# cubex_radio.net
KiCad netlist of a schematic drawn in EAGLE
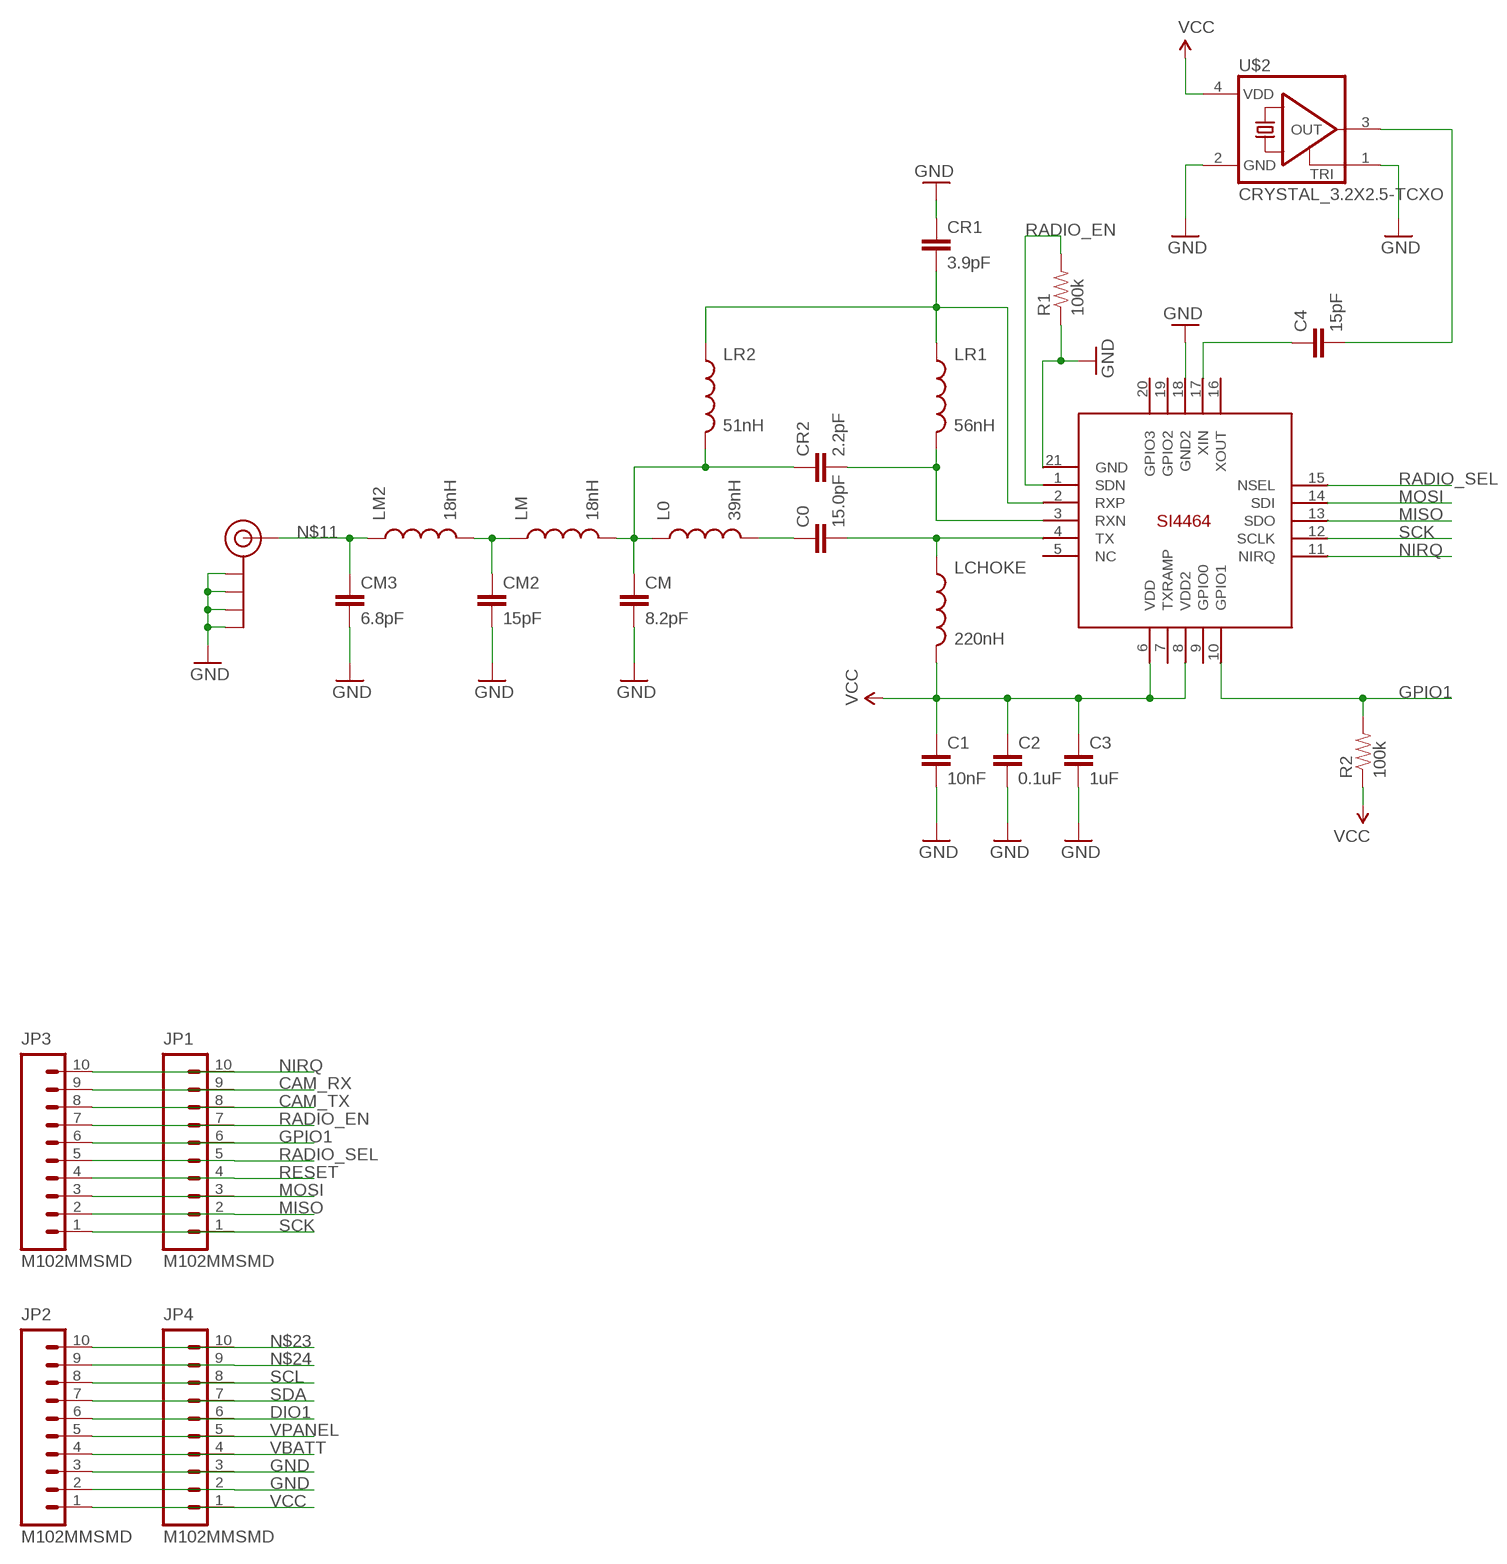
[diagram p0: schematic, sheet 1]

(export (version "E")
  (design (tool "Eeschema 10.0.6"))
  (components
    (comp (ref "C0")
      (value "15.0pF")
      (footprint "eagle-import:0805")
      (libsource (lib "eagle-import") (part "CAP0805"))
    )
    (comp (ref "C1")
      (value "10nF")
      (footprint "eagle-import:0805")
      (libsource (lib "eagle-import") (part "CAP0805"))
    )
    (comp (ref "C2")
      (value "0.1uF")
      (footprint "eagle-import:0805")
      (libsource (lib "eagle-import") (part "CAP0805"))
    )
    (comp (ref "C3")
      (value "1uF")
      (footprint "eagle-import:0805")
      (libsource (lib "eagle-import") (part "CAP0805"))
    )
    (comp (ref "C4")
      (value "15pF")
      (footprint "eagle-import:0805")
      (libsource (lib "eagle-import") (part "CAP0805"))
    )
    (comp (ref "CM")
      (value "8.2pF")
      (footprint "eagle-import:0805")
      (libsource (lib "eagle-import") (part "CAP0805"))
    )
    (comp (ref "CM2")
      (value "15pF")
      (footprint "eagle-import:0805")
      (libsource (lib "eagle-import") (part "CAP0805"))
    )
    (comp (ref "CM3")
      (value "6.8pF")
      (footprint "eagle-import:0805")
      (libsource (lib "eagle-import") (part "CAP0805"))
    )
    (comp (ref "CR1")
      (value "3.9pF")
      (footprint "eagle-import:0805")
      (libsource (lib "eagle-import") (part "CAP0805"))
    )
    (comp (ref "CR2")
      (value "2.2pF")
      (footprint "eagle-import:0805")
      (libsource (lib "eagle-import") (part "CAP0805"))
    )
    (comp (ref "J$1")
      (value "SMA_EDGE")
      (footprint "eagle-import:SMA-EDGE")
      (libsource (lib "eagle-import") (part "SMA_EDGE"))
    )
    (comp (ref "JP1")
      (value "M102MMSMD")
      (footprint "eagle-import:1X10-2MM-SMD")
      (libsource (lib "eagle-import") (part "M102MMSMD"))
    )
    (comp (ref "JP2")
      (value "M102MMSMD")
      (footprint "eagle-import:1X10-2MM-SMD")
      (libsource (lib "eagle-import") (part "M102MMSMD"))
    )
    (comp (ref "JP3")
      (value "M102MMSMD")
      (footprint "eagle-import:1X10-2MM-SMD")
      (libsource (lib "eagle-import") (part "M102MMSMD"))
    )
    (comp (ref "JP4")
      (value "M102MMSMD")
      (footprint "eagle-import:1X10-2MM-SMD")
      (libsource (lib "eagle-import") (part "M102MMSMD"))
    )
    (comp (ref "L0")
      (value "39nH")
      (footprint "eagle-import:0805")
      (libsource (lib "eagle-import") (part "INDUCTOR0805"))
    )
    (comp (ref "LCHOKE")
      (value "220nH")
      (footprint "eagle-import:0805")
      (libsource (lib "eagle-import") (part "INDUCTOR0805"))
    )
    (comp (ref "LM")
      (value "18nH")
      (footprint "eagle-import:0805")
      (libsource (lib "eagle-import") (part "INDUCTOR0805"))
    )
    (comp (ref "LM2")
      (value "18nH")
      (footprint "eagle-import:0805")
      (libsource (lib "eagle-import") (part "INDUCTOR0805"))
    )
    (comp (ref "LR1")
      (value "56nH")
      (footprint "eagle-import:0805")
      (libsource (lib "eagle-import") (part "INDUCTOR0805"))
    )
    (comp (ref "LR2")
      (value "51nH")
      (footprint "eagle-import:0805")
      (libsource (lib "eagle-import") (part "INDUCTOR0805"))
    )
    (comp (ref "R1")
      (value "100k")
      (footprint "eagle-import:0805")
      (libsource (lib "eagle-import") (part "RESISTOR0805-RES"))
    )
    (comp (ref "R2")
      (value "100k")
      (footprint "eagle-import:0805")
      (libsource (lib "eagle-import") (part "RESISTOR0805-RES"))
    )
    (comp (ref "U$1")
      (value "SI4464")
      (footprint "eagle-import:QFN20+GNDPAD")
      (libsource (lib "eagle-import") (part "SI4464"))
    )
    (comp (ref "U$2")
      (value "CRYSTAL_3.2X2.5-TCXO")
      (footprint "eagle-import:CRYSTAL_3.2X2.5-TCXO")
      (libsource (lib "eagle-import") (part "CRYSTAL_3.2X2.5-TCXO"))
    )
  )
  (nets
    (net (code "1") (name "/CAM_RX") (class "Default")
      (node (ref "JP1") (pin "9") (pinfunction "9_9") (pintype "passive"))
      (node (ref "JP3") (pin "9") (pinfunction "9_9") (pintype "passive"))
    )
    (net (code "2") (name "/CAM_TX") (class "Default")
      (node (ref "JP1") (pin "8") (pinfunction "8_8") (pintype "passive"))
      (node (ref "JP3") (pin "8") (pinfunction "8_8") (pintype "passive"))
    )
    (net (code "3") (name "/DIO1") (class "Default")
      (node (ref "JP2") (pin "6") (pinfunction "6_6") (pintype "passive"))
      (node (ref "JP4") (pin "6") (pinfunction "6_6") (pintype "passive"))
    )
    (net (code "4") (name "/GPIO1") (class "Default")
      (node (ref "JP1") (pin "6") (pinfunction "6_6") (pintype "passive"))
      (node (ref "JP3") (pin "6") (pinfunction "6_6") (pintype "passive"))
      (node (ref "R2") (pin "2") (pinfunction "2_2") (pintype "passive"))
      (node (ref "U$1") (pin "10") (pinfunction "GPIO1_10") (pintype "bidirectional"))
    )
    (net (code "5") (name "/MISO") (class "Default")
      (node (ref "JP1") (pin "2") (pinfunction "2_2") (pintype "passive"))
      (node (ref "JP3") (pin "2") (pinfunction "2_2") (pintype "passive"))
      (node (ref "U$1") (pin "13") (pinfunction "SDO_13") (pintype "bidirectional"))
    )
    (net (code "6") (name "/MOSI") (class "Default")
      (node (ref "JP1") (pin "3") (pinfunction "3_3") (pintype "passive"))
      (node (ref "JP3") (pin "3") (pinfunction "3_3") (pintype "passive"))
      (node (ref "U$1") (pin "14") (pinfunction "SDI_14") (pintype "bidirectional"))
    )
    (net (code "7") (name "/N$11") (class "Default")
      (node (ref "CM3") (pin "1") (pinfunction "1_1") (pintype "passive"))
      (node (ref "J$1") (pin "SIG") (pinfunction "SIGNAL_SIG") (pintype "bidirectional"))
      (node (ref "LM2") (pin "1") (pinfunction "1_1") (pintype "passive"))
    )
    (net (code "8") (name "/N$23") (class "Default")
      (node (ref "JP2") (pin "10") (pinfunction "10_10") (pintype "passive"))
      (node (ref "JP4") (pin "10") (pinfunction "10_10") (pintype "passive"))
    )
    (net (code "9") (name "/N$24") (class "Default")
      (node (ref "JP2") (pin "9") (pinfunction "9_9") (pintype "passive"))
      (node (ref "JP4") (pin "9") (pinfunction "9_9") (pintype "passive"))
    )
    (net (code "10") (name "/NIRQ") (class "Default")
      (node (ref "JP1") (pin "10") (pinfunction "10_10") (pintype "passive"))
      (node (ref "JP3") (pin "10") (pinfunction "10_10") (pintype "passive"))
      (node (ref "U$1") (pin "11") (pinfunction "NIRQ_11") (pintype "bidirectional"))
    )
    (net (code "11") (name "/RADIO_EN") (class "Default")
      (node (ref "JP1") (pin "7") (pinfunction "7_7") (pintype "passive"))
      (node (ref "JP3") (pin "7") (pinfunction "7_7") (pintype "passive"))
      (node (ref "R1") (pin "2") (pinfunction "2_2") (pintype "passive"))
      (node (ref "U$1") (pin "1") (pinfunction "SDN_1") (pintype "bidirectional"))
    )
    (net (code "12") (name "/RADIO_SEL") (class "Default")
      (node (ref "JP1") (pin "5") (pinfunction "5_5") (pintype "passive"))
      (node (ref "JP3") (pin "5") (pinfunction "5_5") (pintype "passive"))
      (node (ref "U$1") (pin "15") (pinfunction "NSEL_15") (pintype "bidirectional"))
    )
    (net (code "13") (name "/RESET") (class "Default")
      (node (ref "JP1") (pin "4") (pinfunction "4_4") (pintype "passive"))
      (node (ref "JP3") (pin "4") (pinfunction "4_4") (pintype "passive"))
    )
    (net (code "14") (name "/SCK") (class "Default")
      (node (ref "JP1") (pin "1") (pinfunction "1_1") (pintype "passive"))
      (node (ref "JP3") (pin "1") (pinfunction "1_1") (pintype "passive"))
      (node (ref "U$1") (pin "12") (pinfunction "SCLK_12") (pintype "bidirectional"))
    )
    (net (code "15") (name "/SCL") (class "Default")
      (node (ref "JP2") (pin "8") (pinfunction "8_8") (pintype "passive"))
      (node (ref "JP4") (pin "8") (pinfunction "8_8") (pintype "passive"))
    )
    (net (code "16") (name "/SDA") (class "Default")
      (node (ref "JP2") (pin "7") (pinfunction "7_7") (pintype "passive"))
      (node (ref "JP4") (pin "7") (pinfunction "7_7") (pintype "passive"))
    )
    (net (code "17") (name "/VBATT") (class "Default")
      (node (ref "JP2") (pin "4") (pinfunction "4_4") (pintype "passive"))
      (node (ref "JP4") (pin "4") (pinfunction "4_4") (pintype "passive"))
    )
    (net (code "18") (name "/VPANEL") (class "Default")
      (node (ref "JP2") (pin "5") (pinfunction "5_5") (pintype "passive"))
      (node (ref "JP4") (pin "5") (pinfunction "5_5") (pintype "passive"))
    )
    (net (code "19") (name "GND") (class "Default")
      (node (ref "C1") (pin "2") (pinfunction "2_2") (pintype "passive"))
      (node (ref "C2") (pin "2") (pinfunction "2_2") (pintype "passive"))
      (node (ref "C3") (pin "2") (pinfunction "2_2") (pintype "passive"))
      (node (ref "CM") (pin "2") (pinfunction "2_2") (pintype "passive"))
      (node (ref "CM2") (pin "2") (pinfunction "2_2") (pintype "passive"))
      (node (ref "CM3") (pin "2") (pinfunction "2_2") (pintype "passive"))
      (node (ref "CR1") (pin "1") (pinfunction "1_1") (pintype "passive"))
      (node (ref "J$1") (pin "GND@0") (pinfunction "GND_GND@0") (pintype "bidirectional"))
      (node (ref "J$1") (pin "GND@1") (pinfunction "GND_GND@1") (pintype "bidirectional"))
      (node (ref "J$1") (pin "GND@2") (pinfunction "GND_GND@2") (pintype "bidirectional"))
      (node (ref "J$1") (pin "GND@3") (pinfunction "GND_GND@3") (pintype "bidirectional"))
      (node (ref "JP2") (pin "2") (pinfunction "2_2") (pintype "passive"))
      (node (ref "JP2") (pin "3") (pinfunction "3_3") (pintype "passive"))
      (node (ref "JP4") (pin "2") (pinfunction "2_2") (pintype "passive"))
      (node (ref "JP4") (pin "3") (pinfunction "3_3") (pintype "passive"))
      (node (ref "R1") (pin "1") (pinfunction "1_1") (pintype "passive"))
      (node (ref "U$1") (pin "18") (pinfunction "GND2_18") (pintype "bidirectional"))
      (node (ref "U$1") (pin "21") (pinfunction "GND_21") (pintype "bidirectional"))
      (node (ref "U$2") (pin "1") (pinfunction "TRI_1") (pintype "input"))
      (node (ref "U$2") (pin "2") (pinfunction "GND_2") (pintype "power_in"))
    )
    (net (code "20") (name "Net-(C0-Pad1)") (class "Default")
      (node (ref "C0") (pin "1") (pinfunction "1_1") (pintype "passive"))
      (node (ref "L0") (pin "2") (pinfunction "2_2") (pintype "passive"))
    )
    (net (code "21") (name "Net-(CM-Pad1)") (class "Default")
      (node (ref "CM") (pin "1") (pinfunction "1_1") (pintype "passive"))
      (node (ref "CR2") (pin "1") (pinfunction "1_1") (pintype "passive"))
      (node (ref "L0") (pin "1") (pinfunction "1_1") (pintype "passive"))
      (node (ref "LM") (pin "2") (pinfunction "2_2") (pintype "passive"))
      (node (ref "LR2") (pin "2") (pinfunction "2_2") (pintype "passive"))
    )
    (net (code "22") (name "Net-(CM2-Pad1)") (class "Default")
      (node (ref "CM2") (pin "1") (pinfunction "1_1") (pintype "passive"))
      (node (ref "LM") (pin "1") (pinfunction "1_1") (pintype "passive"))
      (node (ref "LM2") (pin "2") (pinfunction "2_2") (pintype "passive"))
    )
    (net (code "23") (name "Net-(U$1-RXN)") (class "Default")
      (node (ref "CR2") (pin "2") (pinfunction "2_2") (pintype "passive"))
      (node (ref "LR1") (pin "2") (pinfunction "2_2") (pintype "passive"))
      (node (ref "U$1") (pin "3") (pinfunction "RXN_3") (pintype "bidirectional"))
    )
    (net (code "24") (name "Net-(U$1-RXP)") (class "Default")
      (node (ref "CR1") (pin "2") (pinfunction "2_2") (pintype "passive"))
      (node (ref "LR1") (pin "1") (pinfunction "1_1") (pintype "passive"))
      (node (ref "LR2") (pin "1") (pinfunction "1_1") (pintype "passive"))
      (node (ref "U$1") (pin "2") (pinfunction "RXP_2") (pintype "bidirectional"))
    )
    (net (code "25") (name "Net-(U$1-TX)") (class "Default")
      (node (ref "C0") (pin "2") (pinfunction "2_2") (pintype "passive"))
      (node (ref "LCHOKE") (pin "1") (pinfunction "1_1") (pintype "passive"))
      (node (ref "U$1") (pin "4") (pinfunction "TX_4") (pintype "bidirectional"))
    )
    (net (code "26") (name "Net-(U$1-XIN)") (class "Default")
      (node (ref "C4") (pin "1") (pinfunction "1_1") (pintype "passive"))
      (node (ref "U$1") (pin "17") (pinfunction "XIN_17") (pintype "bidirectional"))
    )
    (net (code "27") (name "Net-(U$2-OUT)") (class "Default")
      (node (ref "C4") (pin "2") (pinfunction "2_2") (pintype "passive"))
      (node (ref "U$2") (pin "3") (pinfunction "OUT_3") (pintype "output"))
    )
    (net (code "28") (name "VCC") (class "Default")
      (node (ref "C1") (pin "1") (pinfunction "1_1") (pintype "passive"))
      (node (ref "C2") (pin "1") (pinfunction "1_1") (pintype "passive"))
      (node (ref "C3") (pin "1") (pinfunction "1_1") (pintype "passive"))
      (node (ref "JP2") (pin "1") (pinfunction "1_1") (pintype "passive"))
      (node (ref "JP4") (pin "1") (pinfunction "1_1") (pintype "passive"))
      (node (ref "LCHOKE") (pin "2") (pinfunction "2_2") (pintype "passive"))
      (node (ref "R2") (pin "1") (pinfunction "1_1") (pintype "passive"))
      (node (ref "U$1") (pin "6") (pinfunction "VDD_6") (pintype "bidirectional"))
      (node (ref "U$1") (pin "8") (pinfunction "VDD2_8") (pintype "bidirectional"))
      (node (ref "U$2") (pin "4") (pinfunction "VDD_4") (pintype "power_in"))
    )
    (net (code "29") (name "unconnected-(U$1-GPIO0-Pad9)") (class "Default")
      (node (ref "U$1") (pin "9") (pinfunction "GPIO0_9") (pintype "bidirectional"))
    )
    (net (code "30") (name "unconnected-(U$1-GPIO2-Pad19)") (class "Default")
      (node (ref "U$1") (pin "19") (pinfunction "GPIO2_19") (pintype "bidirectional"))
    )
    (net (code "31") (name "unconnected-(U$1-GPIO3-Pad20)") (class "Default")
      (node (ref "U$1") (pin "20") (pinfunction "GPIO3_20") (pintype "bidirectional"))
    )
    (net (code "32") (name "unconnected-(U$1-NC -Pad5)") (class "Default")
      (node (ref "U$1") (pin "5") (pinfunction "NC _5") (pintype "bidirectional"))
    )
    (net (code "33") (name "unconnected-(U$1-TXRAMP-Pad7)") (class "Default")
      (node (ref "U$1") (pin "7") (pinfunction "TXRAMP_7") (pintype "bidirectional"))
    )
    (net (code "34") (name "unconnected-(U$1-XOUT-Pad16)") (class "Default")
      (node (ref "U$1") (pin "16") (pinfunction "XOUT_16") (pintype "bidirectional"))
    )
  )
)
